# adapter-pcb.net
KiCad netlist of a schematic drawn in EAGLE
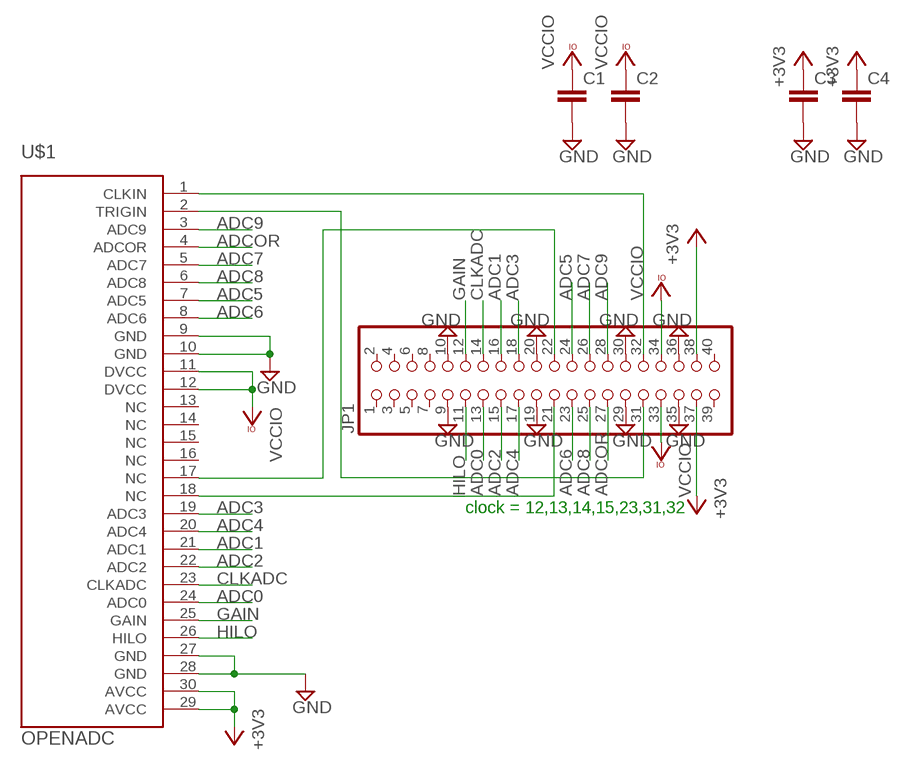
[diagram p0: schematic, sheet 1]

(export (version "E")
  (design (tool "Eeschema 10.0.6"))
  (components
    (comp (ref "C1")
      (value "C-EUC0805")
      (footprint "eagle-import:C0805")
      (libsource (lib "eagle-import") (part "C-EUC0805"))
    )
    (comp (ref "C2")
      (value "C-EUC0805")
      (footprint "eagle-import:C0805")
      (libsource (lib "eagle-import") (part "C-EUC0805"))
    )
    (comp (ref "C3")
      (value "C-EUC0805")
      (footprint "eagle-import:C0805")
      (libsource (lib "eagle-import") (part "C-EUC0805"))
    )
    (comp (ref "C4")
      (value "C-EUC0805")
      (footprint "eagle-import:C0805")
      (libsource (lib "eagle-import") (part "C-EUC0805"))
    )
    (comp (ref "JP1")
      (value "PINHD-2X20")
      (footprint "eagle-import:2X20")
      (libsource (lib "eagle-import") (part "PINHD-2X20"))
    )
    (comp (ref "U$1")
      (value "OPENADC")
      (footprint "eagle-import:OPENADCREV1")
      (libsource (lib "eagle-import") (part "OPENADC"))
    )
  )
  (nets
    (net (code "1") (name "+3V3") (class "Default")
      (node (ref "C3") (pin "1") (pinfunction "1_1") (pintype "passive"))
      (node (ref "C4") (pin "1") (pinfunction "1_1") (pintype "passive"))
      (node (ref "JP1") (pin "37") (pinfunction "37_37") (pintype "passive"))
      (node (ref "JP1") (pin "38") (pinfunction "38_38") (pintype "passive"))
      (node (ref "U$1") (pin "29") (pinfunction "AVCC_29") (pintype "bidirectional"))
      (node (ref "U$1") (pin "30") (pinfunction "AVCC_30") (pintype "bidirectional"))
    )
    (net (code "2") (name "/ADC0") (class "Default")
      (node (ref "JP1") (pin "13") (pinfunction "13_13") (pintype "passive"))
      (node (ref "U$1") (pin "24") (pinfunction "ADC0_24") (pintype "bidirectional"))
    )
    (net (code "3") (name "/ADC1") (class "Default")
      (node (ref "JP1") (pin "16") (pinfunction "16_16") (pintype "passive"))
      (node (ref "U$1") (pin "21") (pinfunction "ADC1_21") (pintype "bidirectional"))
    )
    (net (code "4") (name "/ADC2") (class "Default")
      (node (ref "JP1") (pin "15") (pinfunction "15_15") (pintype "passive"))
      (node (ref "U$1") (pin "22") (pinfunction "ADC2_22") (pintype "bidirectional"))
    )
    (net (code "5") (name "/ADC3") (class "Default")
      (node (ref "JP1") (pin "18") (pinfunction "18_18") (pintype "passive"))
      (node (ref "U$1") (pin "19") (pinfunction "ADC3_19") (pintype "bidirectional"))
    )
    (net (code "6") (name "/ADC4") (class "Default")
      (node (ref "JP1") (pin "17") (pinfunction "17_17") (pintype "passive"))
      (node (ref "U$1") (pin "20") (pinfunction "ADC4_20") (pintype "bidirectional"))
    )
    (net (code "7") (name "/ADC5") (class "Default")
      (node (ref "JP1") (pin "24") (pinfunction "24_24") (pintype "passive"))
      (node (ref "U$1") (pin "7") (pinfunction "ADC5_7") (pintype "bidirectional"))
    )
    (net (code "8") (name "/ADC6") (class "Default")
      (node (ref "JP1") (pin "23") (pinfunction "23_23") (pintype "passive"))
      (node (ref "U$1") (pin "8") (pinfunction "ADC6_8") (pintype "bidirectional"))
    )
    (net (code "9") (name "/ADC7") (class "Default")
      (node (ref "JP1") (pin "26") (pinfunction "26_26") (pintype "passive"))
      (node (ref "U$1") (pin "5") (pinfunction "ADC7_5") (pintype "bidirectional"))
    )
    (net (code "10") (name "/ADC8") (class "Default")
      (node (ref "JP1") (pin "25") (pinfunction "25_25") (pintype "passive"))
      (node (ref "U$1") (pin "6") (pinfunction "ADC8_6") (pintype "bidirectional"))
    )
    (net (code "11") (name "/ADC9") (class "Default")
      (node (ref "JP1") (pin "28") (pinfunction "28_28") (pintype "passive"))
      (node (ref "U$1") (pin "3") (pinfunction "ADC9_3") (pintype "bidirectional"))
    )
    (net (code "12") (name "/ADCOR") (class "Default")
      (node (ref "JP1") (pin "27") (pinfunction "27_27") (pintype "passive"))
      (node (ref "U$1") (pin "4") (pinfunction "ADCOR_4") (pintype "bidirectional"))
    )
    (net (code "13") (name "/CLKADC") (class "Default")
      (node (ref "JP1") (pin "14") (pinfunction "14_14") (pintype "passive"))
      (node (ref "U$1") (pin "23") (pinfunction "CLKADC_23") (pintype "bidirectional"))
    )
    (net (code "14") (name "/GAIN") (class "Default")
      (node (ref "JP1") (pin "12") (pinfunction "12_12") (pintype "passive"))
      (node (ref "U$1") (pin "25") (pinfunction "GAIN_25") (pintype "bidirectional"))
    )
    (net (code "15") (name "/HILO") (class "Default")
      (node (ref "JP1") (pin "11") (pinfunction "11_11") (pintype "passive"))
      (node (ref "U$1") (pin "26") (pinfunction "HILO_26") (pintype "bidirectional"))
    )
    (net (code "16") (name "GND") (class "Default")
      (node (ref "C1") (pin "2") (pinfunction "2_2") (pintype "passive"))
      (node (ref "C2") (pin "2") (pinfunction "2_2") (pintype "passive"))
      (node (ref "C3") (pin "2") (pinfunction "2_2") (pintype "passive"))
      (node (ref "C4") (pin "2") (pinfunction "2_2") (pintype "passive"))
      (node (ref "JP1") (pin "10") (pinfunction "10_10") (pintype "passive"))
      (node (ref "JP1") (pin "19") (pinfunction "19_19") (pintype "passive"))
      (node (ref "JP1") (pin "20") (pinfunction "20_20") (pintype "passive"))
      (node (ref "JP1") (pin "29") (pinfunction "29_29") (pintype "passive"))
      (node (ref "JP1") (pin "30") (pinfunction "30_30") (pintype "passive"))
      (node (ref "JP1") (pin "35") (pinfunction "35_35") (pintype "passive"))
      (node (ref "JP1") (pin "36") (pinfunction "36_36") (pintype "passive"))
      (node (ref "JP1") (pin "9") (pinfunction "9_9") (pintype "passive"))
      (node (ref "U$1") (pin "10") (pinfunction "GND_10") (pintype "bidirectional"))
      (node (ref "U$1") (pin "27") (pinfunction "GND_27") (pintype "bidirectional"))
      (node (ref "U$1") (pin "28") (pinfunction "GND_28") (pintype "bidirectional"))
      (node (ref "U$1") (pin "9") (pinfunction "GND_9") (pintype "bidirectional"))
    )
    (net (code "17") (name "Net-(JP1-Pad21)") (class "Default")
      (node (ref "JP1") (pin "21") (pinfunction "21_21") (pintype "passive"))
      (node (ref "U$1") (pin "18") (pinfunction "NC_18") (pintype "bidirectional"))
    )
    (net (code "18") (name "Net-(JP1-Pad22)") (class "Default")
      (node (ref "JP1") (pin "22") (pinfunction "22_22") (pintype "passive"))
      (node (ref "U$1") (pin "17") (pinfunction "NC_17") (pintype "bidirectional"))
    )
    (net (code "19") (name "Net-(U$1-CLKIN)") (class "Default")
      (node (ref "JP1") (pin "32") (pinfunction "32_32") (pintype "passive"))
      (node (ref "U$1") (pin "1") (pinfunction "CLKIN_1") (pintype "bidirectional"))
    )
    (net (code "20") (name "Net-(U$1-TRIGIN)") (class "Default")
      (node (ref "JP1") (pin "31") (pinfunction "31_31") (pintype "passive"))
      (node (ref "U$1") (pin "2") (pinfunction "TRIGIN_2") (pintype "bidirectional"))
    )
    (net (code "21") (name "VCCIO") (class "Default")
      (node (ref "C1") (pin "1") (pinfunction "1_1") (pintype "passive"))
      (node (ref "C2") (pin "1") (pinfunction "1_1") (pintype "passive"))
      (node (ref "JP1") (pin "33") (pinfunction "33_33") (pintype "passive"))
      (node (ref "JP1") (pin "34") (pinfunction "34_34") (pintype "passive"))
      (node (ref "U$1") (pin "11") (pinfunction "DVCC_11") (pintype "bidirectional"))
      (node (ref "U$1") (pin "12") (pinfunction "DVCC_12") (pintype "bidirectional"))
    )
    (net (code "22") (name "unconnected-(JP1-Pad1)") (class "Default")
      (node (ref "JP1") (pin "1") (pinfunction "1_1") (pintype "passive"))
    )
    (net (code "23") (name "unconnected-(JP1-Pad2)") (class "Default")
      (node (ref "JP1") (pin "2") (pinfunction "2_2") (pintype "passive"))
    )
    (net (code "24") (name "unconnected-(JP1-Pad3)") (class "Default")
      (node (ref "JP1") (pin "3") (pinfunction "3_3") (pintype "passive"))
    )
    (net (code "25") (name "unconnected-(JP1-Pad4)") (class "Default")
      (node (ref "JP1") (pin "4") (pinfunction "4_4") (pintype "passive"))
    )
    (net (code "26") (name "unconnected-(JP1-Pad5)") (class "Default")
      (node (ref "JP1") (pin "5") (pinfunction "5_5") (pintype "passive"))
    )
    (net (code "27") (name "unconnected-(JP1-Pad6)") (class "Default")
      (node (ref "JP1") (pin "6") (pinfunction "6_6") (pintype "passive"))
    )
    (net (code "28") (name "unconnected-(JP1-Pad7)") (class "Default")
      (node (ref "JP1") (pin "7") (pinfunction "7_7") (pintype "passive"))
    )
    (net (code "29") (name "unconnected-(JP1-Pad8)") (class "Default")
      (node (ref "JP1") (pin "8") (pinfunction "8_8") (pintype "passive"))
    )
    (net (code "30") (name "unconnected-(JP1-Pad39)") (class "Default")
      (node (ref "JP1") (pin "39") (pinfunction "39_39") (pintype "passive"))
    )
    (net (code "31") (name "unconnected-(JP1-Pad40)") (class "Default")
      (node (ref "JP1") (pin "40") (pinfunction "40_40") (pintype "passive"))
    )
    (net (code "32") (name "unconnected-(U$1-NC-Pad13)") (class "Default")
      (node (ref "U$1") (pin "13") (pinfunction "NC_13") (pintype "bidirectional"))
    )
    (net (code "33") (name "unconnected-(U$1-NC-Pad14)") (class "Default")
      (node (ref "U$1") (pin "14") (pinfunction "NC_14") (pintype "bidirectional"))
    )
    (net (code "34") (name "unconnected-(U$1-NC-Pad15)") (class "Default")
      (node (ref "U$1") (pin "15") (pinfunction "NC_15") (pintype "bidirectional"))
    )
    (net (code "35") (name "unconnected-(U$1-NC-Pad16)") (class "Default")
      (node (ref "U$1") (pin "16") (pinfunction "NC_16") (pintype "bidirectional"))
    )
  )
)
